# Lan.net
KiCad netlist of a schematic drawn in Altium Designer
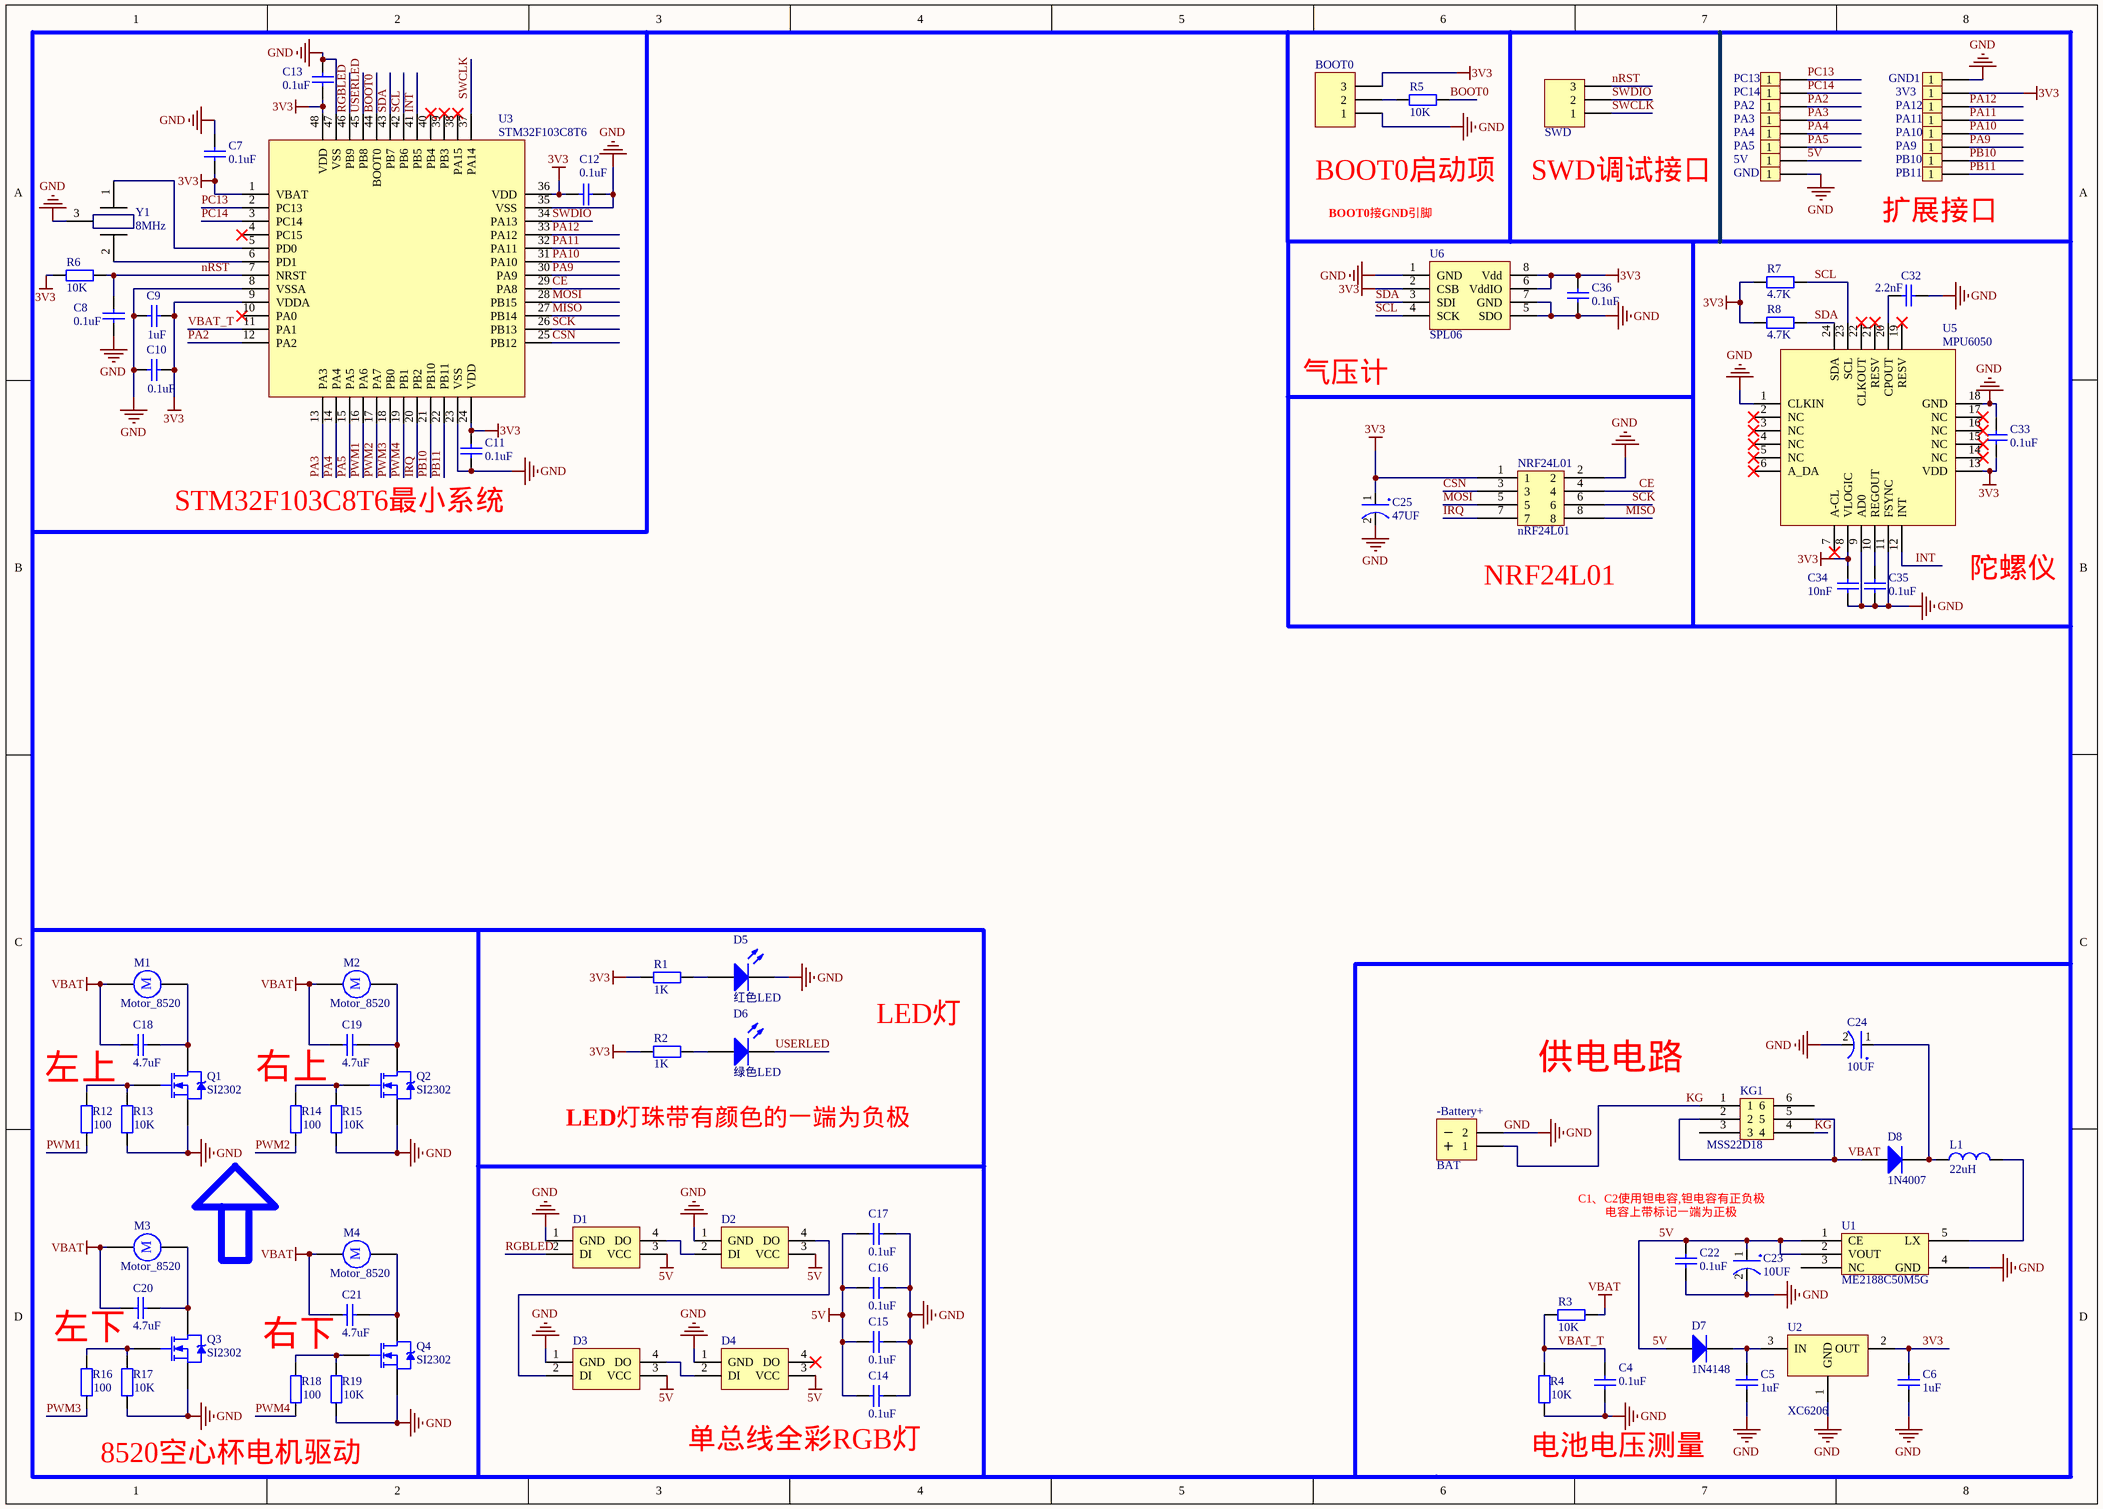
[diagram p0: Lan.SchDoc]

(export (version "E")
  (design (tool "Eeschema 10.0.6"))
  (components
    (comp (ref "-Battery+")
      (value "BAT")
      (footprint "BAT")
      (description "两脚排针")
      (fields (field (name "PUBLISHER") "mazhongwei"))
      (libsource (lib "RoboFly") (part "BAT"))
    )
    (comp (ref "3V3")
      (value "Header 1")
      (footprint "HEADER1")
      (description "单排针")
      (fields (field (name "PUBLISHER") "Altium Limited"))
      (libsource (lib "RoboFly") (part "Header 1"))
    )
    (comp (ref "5V")
      (value "Header 1")
      (footprint "HEADER1")
      (description "单排针")
      (fields (field (name "PUBLISHER") "Altium Limited"))
      (libsource (lib "RoboFly") (part "Header 1"))
    )
    (comp (ref "BOOT0")
      (value "BOOT")
      (footprint "HEADER1X3")
      (description "三脚排针")
      (fields (field (name "PUBLISHER") "Altium Limited"))
      (libsource (lib "RoboFly") (part "Header 3"))
    )
    (comp (ref "C4")
      (value "0.1uF")
      (footprint "C_0603")
      (description "0603贴片电容")
      (fields (field (name "PUBLISHER") "Altium Limited"))
      (libsource (lib "RoboFly") (part "C_0603"))
    )
    (comp (ref "C5")
      (value "1uF")
      (footprint "C_0603")
      (description "0603贴片电容")
      (fields (field (name "PUBLISHER") "Altium Limited"))
      (libsource (lib "RoboFly") (part "C_0603"))
    )
    (comp (ref "C6")
      (value "1uF")
      (footprint "C_0603")
      (description "0603贴片电容")
      (fields (field (name "PUBLISHER") "Altium Limited"))
      (libsource (lib "RoboFly") (part "C_0603"))
    )
    (comp (ref "C7")
      (value "0.1uF")
      (footprint "C_0603")
      (description "0603贴片电容")
      (fields (field (name "PUBLISHER") "Altium Limited"))
      (libsource (lib "RoboFly") (part "C_0603"))
    )
    (comp (ref "C8")
      (value "0.1uF")
      (footprint "C_0603")
      (description "0603贴片电容")
      (fields (field (name "PUBLISHER") "Altium Limited"))
      (libsource (lib "RoboFly") (part "C_0603"))
    )
    (comp (ref "C9")
      (value "1uF")
      (footprint "C_0603")
      (description "0603贴片电容")
      (fields (field (name "PUBLISHER") "Altium Limited"))
      (libsource (lib "RoboFly") (part "C_0603"))
    )
    (comp (ref "C10")
      (value "0.1uF")
      (footprint "C_0603")
      (description "0603贴片电容")
      (fields (field (name "PUBLISHER") "Altium Limited"))
      (libsource (lib "RoboFly") (part "C_0603"))
    )
    (comp (ref "C11")
      (value "0.1uF")
      (footprint "C_0603")
      (description "0603贴片电容")
      (fields (field (name "PUBLISHER") "Altium Limited"))
      (libsource (lib "RoboFly") (part "C_0603"))
    )
    (comp (ref "C12")
      (value "0.1uF")
      (footprint "C_0603")
      (description "0603贴片电容")
      (fields (field (name "PUBLISHER") "Altium Limited"))
      (libsource (lib "RoboFly") (part "C_0603"))
    )
    (comp (ref "C13")
      (value "0.1uF")
      (footprint "C_0603")
      (description "0603贴片电容")
      (fields (field (name "PUBLISHER") "Altium Limited"))
      (libsource (lib "RoboFly") (part "C_0603"))
    )
    (comp (ref "C14")
      (value "0.1uF")
      (footprint "C_0603")
      (description "0603贴片电容")
      (fields (field (name "PUBLISHER") "Altium Limited"))
      (libsource (lib "RoboFly") (part "C_0603"))
    )
    (comp (ref "C15")
      (value "0.1uF")
      (footprint "C_0603")
      (description "0603贴片电容")
      (fields (field (name "PUBLISHER") "Altium Limited"))
      (libsource (lib "RoboFly") (part "C_0603"))
    )
    (comp (ref "C16")
      (value "0.1uF")
      (footprint "C_0603")
      (description "0603贴片电容")
      (fields (field (name "PUBLISHER") "Altium Limited"))
      (libsource (lib "RoboFly") (part "C_0603"))
    )
    (comp (ref "C17")
      (value "0.1uF")
      (footprint "C_0603")
      (description "0603贴片电容")
      (fields (field (name "PUBLISHER") "Altium Limited"))
      (libsource (lib "RoboFly") (part "C_0603"))
    )
    (comp (ref "C18")
      (value "4.7uF")
      (footprint "C_0603")
      (description "0603贴片电容")
      (fields (field (name "PUBLISHER") "Altium Limited"))
      (libsource (lib "RoboFly") (part "C_0603"))
    )
    (comp (ref "C19")
      (value "4.7uF")
      (footprint "C_0603")
      (description "0603贴片电容")
      (fields (field (name "PUBLISHER") "Altium Limited"))
      (libsource (lib "RoboFly") (part "C_0603"))
    )
    (comp (ref "C20")
      (value "4.7uF")
      (footprint "C_0603")
      (description "0603贴片电容")
      (fields (field (name "PUBLISHER") "Altium Limited"))
      (libsource (lib "RoboFly") (part "C_0603"))
    )
    (comp (ref "C21")
      (value "4.7uF")
      (footprint "C_0603")
      (description "0603贴片电容")
      (fields (field (name "PUBLISHER") "Altium Limited"))
      (libsource (lib "RoboFly") (part "C_0603"))
    )
    (comp (ref "C22")
      (value "0.1uF")
      (footprint "C_0603")
      (description "0603贴片电容")
      (fields (field (name "PUBLISHER") "Altium Limited"))
      (libsource (lib "RoboFly") (part "C_0603"))
    )
    (comp (ref "C23")
      (value "10UF")
      (footprint "capacity")
      (description "3216钽电容")
      (libsource (lib "RoboFly") (part "capacity"))
    )
    (comp (ref "C24")
      (value "10UF")
      (footprint "capacity")
      (description "3216钽电容")
      (libsource (lib "RoboFly") (part "capacity"))
    )
    (comp (ref "C25")
      (value "47UF")
      (footprint "capacity")
      (description "3216钽电容")
      (libsource (lib "RoboFly") (part "capacity"))
    )
    (comp (ref "C32")
      (value "2.2nF")
      (footprint "C_0603")
      (description "0603贴片电容")
      (fields (field (name "PUBLISHER") "Altium Limited"))
      (libsource (lib "RoboFly") (part "C_0603"))
    )
    (comp (ref "C33")
      (value "0.1uF")
      (footprint "C_0603")
      (description "0603贴片电容")
      (fields (field (name "PUBLISHER") "Altium Limited"))
      (libsource (lib "RoboFly") (part "C_0603"))
    )
    (comp (ref "C34")
      (value "10nF")
      (footprint "C_0603")
      (description "0603贴片电容")
      (fields (field (name "PUBLISHER") "Altium Limited"))
      (libsource (lib "RoboFly") (part "C_0603"))
    )
    (comp (ref "C35")
      (value "0.1uF")
      (footprint "C_0603")
      (description "0603贴片电容")
      (fields (field (name "PUBLISHER") "Altium Limited"))
      (libsource (lib "RoboFly") (part "C_0603"))
    )
    (comp (ref "C36")
      (value "0.1uF")
      (footprint "C_0603")
      (description "0603贴片电容")
      (fields (field (name "PUBLISHER") "Altium Limited"))
      (libsource (lib "RoboFly") (part "C_0603"))
    )
    (comp (ref "D1")
      (value "WS2812B")
      (footprint "RGB_LED_5050")
      (description "单总线全彩RGB灯")
      (fields (field (name "PUBLISHER") "mazhongwei"))
      (libsource (lib "RoboFly") (part "P923D"))
    )
    (comp (ref "D2")
      (value "WS2812B")
      (footprint "RGB_LED_5050")
      (description "单总线全彩RGB灯")
      (fields (field (name "PUBLISHER") "mazhongwei"))
      (libsource (lib "RoboFly") (part "P923D"))
    )
    (comp (ref "D3")
      (value "WS2812B")
      (footprint "RGB_LED_5050")
      (description "单总线全彩RGB灯")
      (fields (field (name "PUBLISHER") "mazhongwei"))
      (libsource (lib "RoboFly") (part "P923D"))
    )
    (comp (ref "D4")
      (value "WS2812B")
      (footprint "RGB_LED_5050")
      (description "单总线全彩RGB灯")
      (fields (field (name "PUBLISHER") "mazhongwei"))
      (libsource (lib "RoboFly") (part "P923D"))
    )
    (comp (ref "D5")
      (value "红色LED")
      (footprint "LED-0603")
      (description "发光二极管")
      (fields (field (name "PUBLISHER") "Altium Limited"))
      (libsource (lib "RoboFly") (part "LED 0603"))
    )
    (comp (ref "D6")
      (value "绿色LED")
      (footprint "LED-0603")
      (description "发光二极管")
      (fields (field (name "PUBLISHER") "Altium Limited"))
      (libsource (lib "RoboFly") (part "LED 0603"))
    )
    (comp (ref "D7")
      (value "1N4148")
      (footprint "SOD-123")
      (description "Default Diode")
      (fields (field (name "PUBLISHER") "mazhongwei"))
      (libsource (lib "RoboFly") (part "Diode"))
    )
    (comp (ref "D8")
      (value "1N4007")
      (footprint "SMA")
      (description "Default Diode")
      (fields (field (name "PUBLISHER") "mazhongwei"))
      (libsource (lib "RoboFly") (part "Diode"))
    )
    (comp (ref "GND")
      (value "Header 1")
      (footprint "HEADER1")
      (description "单排针")
      (fields (field (name "PUBLISHER") "Altium Limited"))
      (libsource (lib "RoboFly") (part "Header 1"))
    )
    (comp (ref "GND1")
      (value "Header 1")
      (footprint "HEADER1")
      (description "单排针")
      (fields (field (name "PUBLISHER") "Altium Limited"))
      (libsource (lib "RoboFly") (part "Header 1"))
    )
    (comp (ref "KG1")
      (value "MSS22D18")
      (footprint "MSS22D18")
      (description "拨动开关")
      (libsource (lib "RoboFly") (part "MSS22D18"))
    )
    (comp (ref "L1")
      (value "22uH")
      (footprint "22uH")
      (description "电感")
      (fields (field (name "PUBLISHER") "Altium Limited"))
      (libsource (lib "RoboFly") (part "Inductor"))
    )
    (comp (ref "M1")
      (value "Motor_8520")
      (footprint "MOTOR")
      (description "Motor, General Kind")
      (fields (field (name "PUBLISHER") "mazhongwei"))
      (libsource (lib "RoboFly") (part "Motor_720"))
    )
    (comp (ref "M2")
      (value "Motor_8520")
      (footprint "MOTOR")
      (description "Motor, General Kind")
      (fields (field (name "PUBLISHER") "mazhongwei"))
      (libsource (lib "RoboFly") (part "Motor_720"))
    )
    (comp (ref "M3")
      (value "Motor_8520")
      (footprint "MOTOR")
      (description "Motor, General Kind")
      (fields (field (name "PUBLISHER") "mazhongwei"))
      (libsource (lib "RoboFly") (part "Motor_720"))
    )
    (comp (ref "M4")
      (value "Motor_8520")
      (footprint "MOTOR")
      (description "Motor, General Kind")
      (fields (field (name "PUBLISHER") "mazhongwei"))
      (libsource (lib "RoboFly") (part "Motor_720"))
    )
    (comp (ref "NRF24L01")
      (value "nRF24L01")
      (footprint "NRF24L01")
      (description "2.4G模块")
      (libsource (lib "RoboFly") (part "nRF24L01"))
    )
    (comp (ref "PA2")
      (value "Header 1")
      (footprint "HEADER1")
      (description "单排针")
      (fields (field (name "PUBLISHER") "Altium Limited"))
      (libsource (lib "RoboFly") (part "Header 1"))
    )
    (comp (ref "PA3")
      (value "Header 1")
      (footprint "HEADER1")
      (description "单排针")
      (fields (field (name "PUBLISHER") "Altium Limited"))
      (libsource (lib "RoboFly") (part "Header 1"))
    )
    (comp (ref "PA4")
      (value "Header 1")
      (footprint "HEADER1")
      (description "单排针")
      (fields (field (name "PUBLISHER") "Altium Limited"))
      (libsource (lib "RoboFly") (part "Header 1"))
    )
    (comp (ref "PA5")
      (value "Header 1")
      (footprint "HEADER1")
      (description "单排针")
      (fields (field (name "PUBLISHER") "Altium Limited"))
      (libsource (lib "RoboFly") (part "Header 1"))
    )
    (comp (ref "PA9")
      (value "Header 1")
      (footprint "HEADER1")
      (description "单排针")
      (fields (field (name "PUBLISHER") "Altium Limited"))
      (libsource (lib "RoboFly") (part "Header 1"))
    )
    (comp (ref "PA10")
      (value "Header 1")
      (footprint "HEADER1")
      (description "单排针")
      (fields (field (name "PUBLISHER") "Altium Limited"))
      (libsource (lib "RoboFly") (part "Header 1"))
    )
    (comp (ref "PA11")
      (value "Header 1")
      (footprint "HEADER1")
      (description "单排针")
      (fields (field (name "PUBLISHER") "Altium Limited"))
      (libsource (lib "RoboFly") (part "Header 1"))
    )
    (comp (ref "PA12")
      (value "Header 1")
      (footprint "HEADER1")
      (description "单排针")
      (fields (field (name "PUBLISHER") "Altium Limited"))
      (libsource (lib "RoboFly") (part "Header 1"))
    )
    (comp (ref "PB10")
      (value "Header 1")
      (footprint "HEADER1")
      (description "单排针")
      (fields (field (name "PUBLISHER") "Altium Limited"))
      (libsource (lib "RoboFly") (part "Header 1"))
    )
    (comp (ref "PB11")
      (value "Header 1")
      (footprint "HEADER1")
      (description "单排针")
      (fields (field (name "PUBLISHER") "Altium Limited"))
      (libsource (lib "RoboFly") (part "Header 1"))
    )
    (comp (ref "PC13")
      (value "Header 1")
      (footprint "HEADER1")
      (description "单排针")
      (fields (field (name "PUBLISHER") "Altium Limited"))
      (libsource (lib "RoboFly") (part "Header 1"))
    )
    (comp (ref "PC14")
      (value "Header 1")
      (footprint "HEADER1")
      (description "单排针")
      (fields (field (name "PUBLISHER") "Altium Limited"))
      (libsource (lib "RoboFly") (part "Header 1"))
    )
    (comp (ref "Q1")
      (value "SI2302")
      (footprint "SOT-23(SOT-23-3)")
      (description "N-Channel Power MOSFET")
      (fields (field (name "PUBLISHER") "mazhongwei"))
      (libsource (lib "RoboFly") (part "SI2302"))
    )
    (comp (ref "Q2")
      (value "SI2302")
      (footprint "SOT-23(SOT-23-3)")
      (description "N-Channel Power MOSFET")
      (fields (field (name "PUBLISHER") "mazhongwei"))
      (libsource (lib "RoboFly") (part "SI2302"))
    )
    (comp (ref "Q3")
      (value "SI2302")
      (footprint "SOT-23(SOT-23-3)")
      (description "N-Channel Power MOSFET")
      (fields (field (name "PUBLISHER") "mazhongwei"))
      (libsource (lib "RoboFly") (part "SI2302"))
    )
    (comp (ref "Q4")
      (value "SI2302")
      (footprint "SOT-23(SOT-23-3)")
      (description "N-Channel Power MOSFET")
      (fields (field (name "PUBLISHER") "mazhongwei"))
      (libsource (lib "RoboFly") (part "SI2302"))
    )
    (comp (ref "R1")
      (value "1K")
      (footprint "R_0603")
      (description "0603贴片电阻")
      (fields (field (name "PUBLISHER") "Altium Limited"))
      (libsource (lib "Lan") (part "R_0603"))
    )
    (comp (ref "R2")
      (value "1K")
      (footprint "R_0603")
      (description "0603贴片电阻")
      (fields (field (name "PUBLISHER") "Altium Limited"))
      (libsource (lib "Lan") (part "R_0603"))
    )
    (comp (ref "R3")
      (value "10K")
      (footprint "R_0603")
      (description "0603贴片电阻")
      (fields (field (name "PUBLISHER") "Altium Limited"))
      (libsource (lib "Lan") (part "R_0603"))
    )
    (comp (ref "R4")
      (value "10K")
      (footprint "R_0603")
      (description "0603贴片电阻")
      (fields (field (name "PUBLISHER") "Altium Limited"))
      (libsource (lib "") (part "R_0603_1"))
    )
    (comp (ref "R5")
      (value "10K")
      (footprint "R_0603")
      (description "0603贴片电阻")
      (fields (field (name "PUBLISHER") "Altium Limited"))
      (libsource (lib "Lan") (part "R_0603"))
    )
    (comp (ref "R6")
      (value "10K")
      (footprint "R_0603")
      (description "0603贴片电阻")
      (fields (field (name "PUBLISHER") "Altium Limited"))
      (libsource (lib "") (part "R_0603_2"))
    )
    (comp (ref "R7")
      (value "4.7K")
      (footprint "R_0603")
      (description "0603贴片电阻")
      (fields (field (name "PUBLISHER") "Altium Limited"))
      (libsource (lib "Lan") (part "R_0603"))
    )
    (comp (ref "R8")
      (value "4.7K")
      (footprint "R_0603")
      (description "0603贴片电阻")
      (fields (field (name "PUBLISHER") "Altium Limited"))
      (libsource (lib "Lan") (part "R_0603"))
    )
    (comp (ref "R12")
      (value "100")
      (footprint "R_0603")
      (description "0603贴片电阻")
      (fields (field (name "PUBLISHER") "Altium Limited"))
      (libsource (lib "") (part "R_0603_1"))
    )
    (comp (ref "R13")
      (value "10K")
      (footprint "R_0603")
      (description "0603贴片电阻")
      (fields (field (name "PUBLISHER") "Altium Limited"))
      (libsource (lib "") (part "R_0603_1"))
    )
    (comp (ref "R14")
      (value "100")
      (footprint "R_0603")
      (description "0603贴片电阻")
      (fields (field (name "PUBLISHER") "Altium Limited"))
      (libsource (lib "") (part "R_0603_1"))
    )
    (comp (ref "R15")
      (value "10K")
      (footprint "R_0603")
      (description "0603贴片电阻")
      (fields (field (name "PUBLISHER") "Altium Limited"))
      (libsource (lib "") (part "R_0603_1"))
    )
    (comp (ref "R16")
      (value "100")
      (footprint "R_0603")
      (description "0603贴片电阻")
      (fields (field (name "PUBLISHER") "Altium Limited"))
      (libsource (lib "") (part "R_0603_1"))
    )
    (comp (ref "R17")
      (value "10K")
      (footprint "R_0603")
      (description "0603贴片电阻")
      (fields (field (name "PUBLISHER") "Altium Limited"))
      (libsource (lib "") (part "R_0603_1"))
    )
    (comp (ref "R18")
      (value "100")
      (footprint "R_0603")
      (description "0603贴片电阻")
      (fields (field (name "PUBLISHER") "Altium Limited"))
      (libsource (lib "") (part "R_0603_1"))
    )
    (comp (ref "R19")
      (value "10K")
      (footprint "R_0603")
      (description "0603贴片电阻")
      (fields (field (name "PUBLISHER") "Altium Limited"))
      (libsource (lib "") (part "R_0603_1"))
    )
    (comp (ref "SWD")
      (value "SWD")
      (footprint "SH1_0X5P_WT")
      (description "三脚排针")
      (fields (field (name "PUBLISHER") "Altium Limited"))
      (libsource (lib "RoboFly") (part "SWD"))
    )
    (comp (ref "U1")
      (value "ME2188C50M5G")
      (footprint "ME2188C50M5G")
      (description "升压IC")
      (libsource (lib "RoboFly") (part "ME2188C50M5G"))
    )
    (comp (ref "U2")
      (value "XC6206")
      (footprint "SOT-23(SOT-23-3)")
      (description "稳压LDO")
      (fields (field (name "PUBLISHER") "mazhongwei"))
      (libsource (lib "Lan") (part "XC6206"))
    )
    (comp (ref "U3")
      (value "STM32F103C8T6")
      (footprint "LQFP-48_7x7x05P")
      (libsource (lib "RoboFly") (part "STM32F103C8T6"))
    )
    (comp (ref "U5")
      (value "MPU6050")
      (footprint "QFN-24_4x4x05P")
      (description "陀螺仪")
      (libsource (lib "RoboFly") (part "MPU6050"))
    )
    (comp (ref "U6")
      (value "SPL06")
      (footprint "LGA-2_5X2MM")
      (description "气压计")
      (fields (field (name "PUBLISHER") "mazhongwei"))
      (libsource (lib "RoboFly") (part "FBM320"))
    )
    (comp (ref "Y1")
      (value "8MHz")
      (footprint "SMD-CSTSE800G52-R0")
      (description "贴片8MHZ晶振")
      (fields (field (name "Comment") "XTAL") (field (name "PUBLISHER") "mazhongwei"))
      (libsource (lib "RoboFly") (part "XTAL_2"))
    )
  )
  (nets
    (net (code "1") (name "/BOOT0") (class "Default")
      (node (ref "R5") (pin "2") (pinfunction "2_2") (pintype "passive"))
      (node (ref "U3") (pin "44") (pinfunction "BOOT0_44") (pintype "passive"))
    )
    (net (code "2") (name "/CE") (class "Default")
      (node (ref "NRF24L01") (pin "4") (pinfunction "4_4") (pintype "passive"))
      (node (ref "U3") (pin "29") (pinfunction "PA8_29") (pintype "passive"))
    )
    (net (code "3") (name "/CSN") (class "Default")
      (node (ref "NRF24L01") (pin "3") (pinfunction "3_3") (pintype "passive"))
      (node (ref "U3") (pin "25") (pinfunction "PB12_25") (pintype "passive"))
    )
    (net (code "4") (name "/INT") (class "Default")
      (node (ref "U3") (pin "41") (pinfunction "PB5_41") (pintype "passive"))
      (node (ref "U5") (pin "12") (pinfunction "INT_12") (pintype "passive"))
    )
    (net (code "5") (name "/IRQ") (class "Default")
      (node (ref "NRF24L01") (pin "7") (pinfunction "7_7") (pintype "passive"))
      (node (ref "U3") (pin "20") (pinfunction "PB2_20") (pintype "passive"))
    )
    (net (code "6") (name "/KG") (class "Default")
      (node (ref "-Battery+") (pin "1") (pinfunction "1_1") (pintype "passive"))
      (node (ref "KG1") (pin "1") (pinfunction "1_1") (pintype "passive"))
      (node (ref "KG1") (pin "4") (pinfunction "4_4") (pintype "passive"))
    )
    (net (code "7") (name "/MISO") (class "Default")
      (node (ref "NRF24L01") (pin "8") (pinfunction "8_8") (pintype "passive"))
      (node (ref "U3") (pin "27") (pinfunction "PB14_27") (pintype "passive"))
    )
    (net (code "8") (name "/MOSI") (class "Default")
      (node (ref "NRF24L01") (pin "5") (pinfunction "5_5") (pintype "passive"))
      (node (ref "U3") (pin "28") (pinfunction "PB15_28") (pintype "passive"))
    )
    (net (code "9") (name "/PA2") (class "Default")
      (node (ref "PA2") (pin "1") (pinfunction "1_1") (pintype "passive"))
      (node (ref "U3") (pin "12") (pinfunction "PA2_12") (pintype "passive"))
    )
    (net (code "10") (name "/PA3") (class "Default")
      (node (ref "PA3") (pin "1") (pinfunction "1_1") (pintype "passive"))
      (node (ref "U3") (pin "13") (pinfunction "PA3_13") (pintype "passive"))
    )
    (net (code "11") (name "/PA4") (class "Default")
      (node (ref "PA4") (pin "1") (pinfunction "1_1") (pintype "passive"))
      (node (ref "U3") (pin "14") (pinfunction "PA4_14") (pintype "passive"))
    )
    (net (code "12") (name "/PA5") (class "Default")
      (node (ref "PA5") (pin "1") (pinfunction "1_1") (pintype "passive"))
      (node (ref "U3") (pin "15") (pinfunction "PA5_15") (pintype "passive"))
    )
    (net (code "13") (name "/PA9") (class "Default")
      (node (ref "PA9") (pin "1") (pinfunction "1_1") (pintype "passive"))
      (node (ref "U3") (pin "30") (pinfunction "PA9_30") (pintype "passive"))
    )
    (net (code "14") (name "/PA10") (class "Default")
      (node (ref "PA10") (pin "1") (pinfunction "1_1") (pintype "passive"))
      (node (ref "U3") (pin "31") (pinfunction "PA10_31") (pintype "passive"))
    )
    (net (code "15") (name "/PA11") (class "Default")
      (node (ref "PA11") (pin "1") (pinfunction "1_1") (pintype "passive"))
      (node (ref "U3") (pin "32") (pinfunction "PA11_32") (pintype "passive"))
    )
    (net (code "16") (name "/PA12") (class "Default")
      (node (ref "PA12") (pin "1") (pinfunction "1_1") (pintype "passive"))
      (node (ref "U3") (pin "33") (pinfunction "PA12_33") (pintype "passive"))
    )
    (net (code "17") (name "/PB10") (class "Default")
      (node (ref "PB10") (pin "1") (pinfunction "1_1") (pintype "passive"))
      (node (ref "U3") (pin "21") (pinfunction "PB10_21") (pintype "passive"))
    )
    (net (code "18") (name "/PB11") (class "Default")
      (node (ref "PB11") (pin "1") (pinfunction "1_1") (pintype "passive"))
      (node (ref "U3") (pin "22") (pinfunction "PB11_22") (pintype "passive"))
    )
    (net (code "19") (name "/PC13") (class "Default")
      (node (ref "PC13") (pin "1") (pinfunction "1_1") (pintype "passive"))
      (node (ref "U3") (pin "2") (pinfunction "PC13_2") (pintype "passive"))
    )
    (net (code "20") (name "/PC14") (class "Default")
      (node (ref "PC14") (pin "1") (pinfunction "1_1") (pintype "passive"))
      (node (ref "U3") (pin "3") (pinfunction "PC14_3") (pintype "passive"))
    )
    (net (code "21") (name "/PWM1") (class "Default")
      (node (ref "R12") (pin "1") (pinfunction "1_1") (pintype "passive"))
      (node (ref "U3") (pin "16") (pinfunction "PA6_16") (pintype "passive"))
    )
    (net (code "22") (name "/PWM2") (class "Default")
      (node (ref "R14") (pin "1") (pinfunction "1_1") (pintype "passive"))
      (node (ref "U3") (pin "17") (pinfunction "PA7_17") (pintype "passive"))
    )
    (net (code "23") (name "/PWM3") (class "Default")
      (node (ref "R16") (pin "1") (pinfunction "1_1") (pintype "passive"))
      (node (ref "U3") (pin "18") (pinfunction "PB0_18") (pintype "passive"))
    )
    (net (code "24") (name "/PWM4") (class "Default")
      (node (ref "R18") (pin "1") (pinfunction "1_1") (pintype "passive"))
      (node (ref "U3") (pin "19") (pinfunction "PB1_19") (pintype "passive"))
    )
    (net (code "25") (name "/RGBLED") (class "Default")
      (node (ref "D1") (pin "2") (pinfunction "DI_2") (pintype "passive"))
      (node (ref "U3") (pin "46") (pinfunction "PB9_46") (pintype "passive"))
    )
    (net (code "26") (name "/SCK") (class "Default")
      (node (ref "NRF24L01") (pin "6") (pinfunction "6_6") (pintype "passive"))
      (node (ref "U3") (pin "26") (pinfunction "PB13_26") (pintype "passive"))
    )
    (net (code "27") (name "/SCL") (class "Default")
      (node (ref "R7") (pin "2") (pinfunction "2_2") (pintype "passive"))
      (node (ref "U3") (pin "42") (pinfunction "PB6_42") (pintype "passive"))
      (node (ref "U5") (pin "23") (pinfunction "SCL_23") (pintype "passive"))
      (node (ref "U6") (pin "4") (pinfunction "SCK_4") (pintype "passive"))
    )
    (net (code "28") (name "/SDA") (class "Default")
      (node (ref "R8") (pin "2") (pinfunction "2_2") (pintype "passive"))
      (node (ref "U3") (pin "43") (pinfunction "PB7_43") (pintype "passive"))
      (node (ref "U5") (pin "24") (pinfunction "SDA_24") (pintype "passive"))
      (node (ref "U6") (pin "3") (pinfunction "SDI_3") (pintype "passive"))
    )
    (net (code "29") (name "/SWCLK") (class "Default")
      (node (ref "SWD") (pin "1") (pinfunction "1_1") (pintype "passive"))
      (node (ref "U3") (pin "37") (pinfunction "PA14_37") (pintype "passive"))
    )
    (net (code "30") (name "/SWDIO") (class "Default")
      (node (ref "SWD") (pin "2") (pinfunction "2_2") (pintype "passive"))
      (node (ref "U3") (pin "34") (pinfunction "PA13_34") (pintype "passive"))
    )
    (net (code "31") (name "/USERLED") (class "Default")
      (node (ref "D6") (pin "2") (pinfunction "2_2") (pintype "passive"))
      (node (ref "U3") (pin "45") (pinfunction "PB8_45") (pintype "passive"))
    )
    (net (code "32") (name "/VBAT_T") (class "Default")
      (node (ref "C4") (pin "2") (pinfunction "2_2") (pintype "passive"))
      (node (ref "R3") (pin "1") (pinfunction "1_1") (pintype "passive"))
      (node (ref "R4") (pin "2") (pinfunction "2_2") (pintype "passive"))
      (node (ref "U3") (pin "11") (pinfunction "PA1_11") (pintype "passive"))
    )
    (net (code "33") (name "/nRST") (class "Default")
      (node (ref "C8") (pin "2") (pinfunction "2_2") (pintype "passive"))
      (node (ref "R6") (pin "1") (pinfunction "1_1") (pintype "passive"))
      (node (ref "SWD") (pin "3") (pinfunction "3_3") (pintype "passive"))
      (node (ref "U3") (pin "7") (pinfunction "NRST_7") (pintype "passive"))
    )
    (net (code "34") (name "3V3") (class "Default")
      (node (ref "3V3") (pin "1") (pinfunction "1_1") (pintype "passive"))
      (node (ref "BOOT0") (pin "3") (pinfunction "3_3") (pintype "passive"))
      (node (ref "C10") (pin "2") (pinfunction "2_2") (pintype "passive"))
      (node (ref "C11") (pin "1") (pinfunction "1_1") (pintype "passive"))
      (node (ref "C12") (pin "2") (pinfunction "2_2") (pintype "passive"))
      (node (ref "C13") (pin "1") (pinfunction "1_1") (pintype "passive"))
      (node (ref "C25") (pin "1") (pinfunction "1_1") (pintype "passive"))
      (node (ref "C33") (pin "2") (pinfunction "2_2") (pintype "passive"))
      (node (ref "C34") (pin "2") (pinfunction "2_2") (pintype "passive"))
      (node (ref "C36") (pin "1") (pinfunction "1_1") (pintype "passive"))
      (node (ref "C6") (pin "1") (pinfunction "1_1") (pintype "passive"))
      (node (ref "C7") (pin "2") (pinfunction "2_2") (pintype "passive"))
      (node (ref "C9") (pin "2") (pinfunction "2_2") (pintype "passive"))
      (node (ref "NRF24L01") (pin "1") (pinfunction "1_1") (pintype "passive"))
      (node (ref "R1") (pin "1") (pinfunction "1_1") (pintype "passive"))
      (node (ref "R2") (pin "1") (pinfunction "1_1") (pintype "passive"))
      (node (ref "R6") (pin "2") (pinfunction "2_2") (pintype "passive"))
      (node (ref "R7") (pin "1") (pinfunction "1_1") (pintype "passive"))
      (node (ref "R8") (pin "1") (pinfunction "1_1") (pintype "passive"))
      (node (ref "U2") (pin "2") (pinfunction "OUT_2") (pintype "passive"))
      (node (ref "U3") (pin "1") (pinfunction "VBAT_1") (pintype "passive"))
      (node (ref "U3") (pin "24") (pinfunction "VDD_24") (pintype "passive"))
      (node (ref "U3") (pin "36") (pinfunction "VDD_36") (pintype "passive"))
      (node (ref "U3") (pin "48") (pinfunction "VDD_48") (pintype "passive"))
      (node (ref "U3") (pin "9") (pinfunction "VDDA_9") (pintype "passive"))
      (node (ref "U5") (pin "13") (pinfunction "VDD_13") (pintype "passive"))
      (node (ref "U5") (pin "8") (pinfunction "VLOGIC_8") (pintype "passive"))
      (node (ref "U6") (pin "2") (pinfunction "CSB_2") (pintype "passive"))
      (node (ref "U6") (pin "6") (pinfunction "VddIO_6") (pintype "passive"))
      (node (ref "U6") (pin "8") (pinfunction "Vdd_8") (pintype "passive"))
    )
    (net (code "35") (name "5V") (class "Default")
      (node (ref "5V") (pin "1") (pinfunction "1_1") (pintype "passive"))
      (node (ref "C14") (pin "2") (pinfunction "2_2") (pintype "passive"))
      (node (ref "C15") (pin "2") (pinfunction "2_2") (pintype "passive"))
      (node (ref "C16") (pin "2") (pinfunction "2_2") (pintype "passive"))
      (node (ref "C17") (pin "2") (pinfunction "2_2") (pintype "passive"))
      (node (ref "C22") (pin "1") (pinfunction "1_1") (pintype "passive"))
      (node (ref "C23") (pin "1") (pinfunction "1_1") (pintype "passive"))
      (node (ref "D1") (pin "3") (pinfunction "VCC_3") (pintype "passive"))
      (node (ref "D2") (pin "3") (pinfunction "VCC_3") (pintype "passive"))
      (node (ref "D3") (pin "3") (pinfunction "VCC_3") (pintype "passive"))
      (node (ref "D4") (pin "3") (pinfunction "VCC_3") (pintype "passive"))
      (node (ref "D7") (pin "1") (pinfunction "A_1") (pintype "passive"))
      (node (ref "U1") (pin "1") (pinfunction "CE_1") (pintype "passive"))
      (node (ref "U1") (pin "2") (pinfunction "VOUT_2") (pintype "passive"))
    )
    (net (code "36") (name "GND") (class "Default")
      (node (ref "-Battery+") (pin "2") (pinfunction "2_2") (pintype "passive"))
      (node (ref "BOOT0") (pin "1") (pinfunction "1_1") (pintype "passive"))
      (node (ref "C10") (pin "1") (pinfunction "1_1") (pintype "passive"))
      (node (ref "C11") (pin "2") (pinfunction "2_2") (pintype "passive"))
      (node (ref "C12") (pin "1") (pinfunction "1_1") (pintype "passive"))
      (node (ref "C13") (pin "2") (pinfunction "2_2") (pintype "passive"))
      (node (ref "C14") (pin "1") (pinfunction "1_1") (pintype "passive"))
      (node (ref "C15") (pin "1") (pinfunction "1_1") (pintype "passive"))
      (node (ref "C16") (pin "1") (pinfunction "1_1") (pintype "passive"))
      (node (ref "C17") (pin "1") (pinfunction "1_1") (pintype "passive"))
      (node (ref "C22") (pin "2") (pinfunction "2_2") (pintype "passive"))
      (node (ref "C23") (pin "2") (pinfunction "2_2") (pintype "passive"))
      (node (ref "C24") (pin "2") (pinfunction "2_2") (pintype "passive"))
      (node (ref "C25") (pin "2") (pinfunction "2_2") (pintype "passive"))
      (node (ref "C32") (pin "1") (pinfunction "1_1") (pintype "passive"))
      (node (ref "C33") (pin "1") (pinfunction "1_1") (pintype "passive"))
      (node (ref "C34") (pin "1") (pinfunction "1_1") (pintype "passive"))
      (node (ref "C35") (pin "2") (pinfunction "2_2") (pintype "passive"))
      (node (ref "C36") (pin "2") (pinfunction "2_2") (pintype "passive"))
      (node (ref "C4") (pin "1") (pinfunction "1_1") (pintype "passive"))
      (node (ref "C5") (pin "2") (pinfunction "2_2") (pintype "passive"))
      (node (ref "C6") (pin "2") (pinfunction "2_2") (pintype "passive"))
      (node (ref "C7") (pin "1") (pinfunction "1_1") (pintype "passive"))
      (node (ref "C8") (pin "1") (pinfunction "1_1") (pintype "passive"))
      (node (ref "C9") (pin "1") (pinfunction "1_1") (pintype "passive"))
      (node (ref "D1") (pin "1") (pinfunction "GND_1") (pintype "passive"))
      (node (ref "D2") (pin "1") (pinfunction "GND_1") (pintype "passive"))
      (node (ref "D3") (pin "1") (pinfunction "GND_1") (pintype "passive"))
      (node (ref "D4") (pin "1") (pinfunction "GND_1") (pintype "passive"))
      (node (ref "D5") (pin "2") (pinfunction "2_2") (pintype "passive"))
      (node (ref "GND") (pin "1") (pinfunction "1_1") (pintype "passive"))
      (node (ref "GND1") (pin "1") (pinfunction "1_1") (pintype "passive"))
      (node (ref "NRF24L01") (pin "2") (pinfunction "2_2") (pintype "passive"))
      (node (ref "Q1") (pin "2") (pinfunction "S_2") (pintype "passive"))
      (node (ref "Q2") (pin "2") (pinfunction "S_2") (pintype "passive"))
      (node (ref "Q3") (pin "2") (pinfunction "S_2") (pintype "passive"))
      (node (ref "Q4") (pin "2") (pinfunction "S_2") (pintype "passive"))
      (node (ref "R13") (pin "1") (pinfunction "1_1") (pintype "passive"))
      (node (ref "R15") (pin "1") (pinfunction "1_1") (pintype "passive"))
      (node (ref "R17") (pin "1") (pinfunction "1_1") (pintype "passive"))
      (node (ref "R19") (pin "1") (pinfunction "1_1") (pintype "passive"))
      (node (ref "R4") (pin "1") (pinfunction "1_1") (pintype "passive"))
      (node (ref "U1") (pin "4") (pinfunction "GND_4") (pintype "passive"))
      (node (ref "U2") (pin "1") (pinfunction "GND_1") (pintype "passive"))
      (node (ref "U3") (pin "23") (pinfunction "VSS_23") (pintype "passive"))
      (node (ref "U3") (pin "35") (pinfunction "VSS_35") (pintype "passive"))
      (node (ref "U3") (pin "47") (pinfunction "VSS_47") (pintype "passive"))
      (node (ref "U3") (pin "8") (pinfunction "VSSA_8") (pintype "passive"))
      (node (ref "U5") (pin "1") (pinfunction "CLKIN_1") (pintype "passive"))
      (node (ref "U5") (pin "11") (pinfunction "FSYNC_11") (pintype "passive"))
      (node (ref "U5") (pin "18") (pinfunction "GND_18") (pintype "passive"))
      (node (ref "U5") (pin "9") (pinfunction "AD0_9") (pintype "passive"))
      (node (ref "U6") (pin "1") (pinfunction "GND_1") (pintype "passive"))
      (node (ref "U6") (pin "5") (pinfunction "SDO_5") (pintype "passive"))
      (node (ref "U6") (pin "7") (pinfunction "GND_7") (pintype "passive"))
      (node (ref "Y1") (pin "3") (pinfunction "3_3") (pintype "passive"))
    )
    (net (code "37") (name "Net-(BOOT0-Pad2)") (class "Default")
      (node (ref "BOOT0") (pin "2") (pinfunction "2_2") (pintype "passive"))
      (node (ref "R5") (pin "1") (pinfunction "1_1") (pintype "passive"))
    )
    (net (code "38") (name "Net-(D1-DO)") (class "Default")
      (node (ref "D1") (pin "4") (pinfunction "DO_4") (pintype "passive"))
      (node (ref "D2") (pin "2") (pinfunction "DI_2") (pintype "passive"))
    )
    (net (code "39") (name "Net-(D2-DO)") (class "Default")
      (node (ref "D2") (pin "4") (pinfunction "DO_4") (pintype "passive"))
      (node (ref "D3") (pin "2") (pinfunction "DI_2") (pintype "passive"))
    )
    (net (code "40") (name "Net-(D3-DO)") (class "Default")
      (node (ref "D3") (pin "4") (pinfunction "DO_4") (pintype "passive"))
      (node (ref "D4") (pin "2") (pinfunction "DI_2") (pintype "passive"))
    )
    (net (code "41") (name "Net-(D5-Pad1)") (class "Default")
      (node (ref "D5") (pin "1") (pinfunction "1_1") (pintype "passive"))
      (node (ref "R1") (pin "2") (pinfunction "2_2") (pintype "passive"))
    )
    (net (code "42") (name "Net-(D6-Pad1)") (class "Default")
      (node (ref "D6") (pin "1") (pinfunction "1_1") (pintype "passive"))
      (node (ref "R2") (pin "2") (pinfunction "2_2") (pintype "passive"))
    )
    (net (code "43") (name "Net-(D7-K)") (class "Default")
      (node (ref "C5") (pin "1") (pinfunction "1_1") (pintype "passive"))
      (node (ref "D7") (pin "2") (pinfunction "K_2") (pintype "passive"))
      (node (ref "U2") (pin "3") (pinfunction "IN_3") (pintype "passive"))
    )
    (net (code "44") (name "Net-(D8-K)") (class "Default")
      (node (ref "C24") (pin "1") (pinfunction "1_1") (pintype "passive"))
      (node (ref "D8") (pin "2") (pinfunction "K_2") (pintype "passive"))
      (node (ref "L1") (pin "1") (pinfunction "1_1") (pintype "passive"))
    )
    (net (code "45") (name "Net-(Q1-D)") (class "Default")
      (node (ref "C18") (pin "1") (pinfunction "1_1") (pintype "passive"))
      (node (ref "M1") (pin "2") (pinfunction "2_2") (pintype "passive"))
      (node (ref "Q1") (pin "3") (pinfunction "D_3") (pintype "passive"))
    )
    (net (code "46") (name "Net-(Q1-G)") (class "Default")
      (node (ref "Q1") (pin "1") (pinfunction "G_1") (pintype "passive"))
      (node (ref "R12") (pin "2") (pinfunction "2_2") (pintype "passive"))
      (node (ref "R13") (pin "2") (pinfunction "2_2") (pintype "passive"))
    )
    (net (code "47") (name "Net-(Q2-D)") (class "Default")
      (node (ref "C19") (pin "1") (pinfunction "1_1") (pintype "passive"))
      (node (ref "M2") (pin "2") (pinfunction "2_2") (pintype "passive"))
      (node (ref "Q2") (pin "3") (pinfunction "D_3") (pintype "passive"))
    )
    (net (code "48") (name "Net-(Q2-G)") (class "Default")
      (node (ref "Q2") (pin "1") (pinfunction "G_1") (pintype "passive"))
      (node (ref "R14") (pin "2") (pinfunction "2_2") (pintype "passive"))
      (node (ref "R15") (pin "2") (pinfunction "2_2") (pintype "passive"))
    )
    (net (code "49") (name "Net-(Q3-D)") (class "Default")
      (node (ref "C20") (pin "1") (pinfunction "1_1") (pintype "passive"))
      (node (ref "M3") (pin "2") (pinfunction "2_2") (pintype "passive"))
      (node (ref "Q3") (pin "3") (pinfunction "D_3") (pintype "passive"))
    )
    (net (code "50") (name "Net-(Q3-G)") (class "Default")
      (node (ref "Q3") (pin "1") (pinfunction "G_1") (pintype "passive"))
      (node (ref "R16") (pin "2") (pinfunction "2_2") (pintype "passive"))
      (node (ref "R17") (pin "2") (pinfunction "2_2") (pintype "passive"))
    )
    (net (code "51") (name "Net-(Q4-D)") (class "Default")
      (node (ref "C21") (pin "1") (pinfunction "1_1") (pintype "passive"))
      (node (ref "M4") (pin "2") (pinfunction "2_2") (pintype "passive"))
      (node (ref "Q4") (pin "3") (pinfunction "D_3") (pintype "passive"))
    )
    (net (code "52") (name "Net-(Q4-G)") (class "Default")
      (node (ref "Q4") (pin "1") (pinfunction "G_1") (pintype "passive"))
      (node (ref "R18") (pin "2") (pinfunction "2_2") (pintype "passive"))
      (node (ref "R19") (pin "2") (pinfunction "2_2") (pintype "passive"))
    )
    (net (code "53") (name "Net-(U1-LX)") (class "Default")
      (node (ref "L1") (pin "2") (pinfunction "2_2") (pintype "passive"))
      (node (ref "U1") (pin "5") (pinfunction "LX_5") (pintype "passive"))
    )
    (net (code "54") (name "Net-(U3-PD0)") (class "Default")
      (node (ref "U3") (pin "5") (pinfunction "PD0_5") (pintype "passive"))
      (node (ref "Y1") (pin "1") (pinfunction "1_1") (pintype "passive"))
    )
    (net (code "55") (name "Net-(U3-PD1)") (class "Default")
      (node (ref "U3") (pin "6") (pinfunction "PD1_6") (pintype "passive"))
      (node (ref "Y1") (pin "2") (pinfunction "2_2") (pintype "passive"))
    )
    (net (code "56") (name "Net-(U5-CPOUT)") (class "Default")
      (node (ref "C32") (pin "2") (pinfunction "2_2") (pintype "passive"))
      (node (ref "U5") (pin "20") (pinfunction "CPOUT_20") (pintype "passive"))
    )
    (net (code "57") (name "Net-(U5-REGOUT)") (class "Default")
      (node (ref "C35") (pin "1") (pinfunction "1_1") (pintype "passive"))
      (node (ref "U5") (pin "10") (pinfunction "REGOUT_10") (pintype "passive"))
    )
    (net (code "58") (name "VBAT") (class "Default")
      (node (ref "C18") (pin "2") (pinfunction "2_2") (pintype "passive"))
      (node (ref "C19") (pin "2") (pinfunction "2_2") (pintype "passive"))
      (node (ref "C20") (pin "2") (pinfunction "2_2") (pintype "passive"))
      (node (ref "C21") (pin "2") (pinfunction "2_2") (pintype "passive"))
      (node (ref "D8") (pin "1") (pinfunction "A_1") (pintype "passive"))
      (node (ref "KG1") (pin "2") (pinfunction "2_2") (pintype "passive"))
      (node (ref "KG1") (pin "5") (pinfunction "5_5") (pintype "passive"))
      (node (ref "M1") (pin "1") (pinfunction "1_1") (pintype "passive"))
      (node (ref "M2") (pin "1") (pinfunction "1_1") (pintype "passive"))
      (node (ref "M3") (pin "1") (pinfunction "1_1") (pintype "passive"))
      (node (ref "M4") (pin "1") (pinfunction "1_1") (pintype "passive"))
      (node (ref "R3") (pin "2") (pinfunction "2_2") (pintype "passive"))
    )
    (net (code "59") (name "unconnected-(D4-DO-Pad4)") (class "Default")
      (node (ref "D4") (pin "4") (pinfunction "DO_4") (pintype "passive+no_connect"))
    )
    (net (code "60") (name "unconnected-(KG1-Pad3)") (class "Default")
      (node (ref "KG1") (pin "3") (pinfunction "3_3") (pintype "passive"))
    )
    (net (code "61") (name "unconnected-(KG1-Pad6)") (class "Default")
      (node (ref "KG1") (pin "6") (pinfunction "6_6") (pintype "passive"))
    )
    (net (code "62") (name "unconnected-(U1-NC-Pad3)") (class "Default")
      (node (ref "U1") (pin "3") (pinfunction "NC_3") (pintype "passive"))
    )
    (net (code "63") (name "unconnected-(U3-PA0-Pad10)") (class "Default")
      (node (ref "U3") (pin "10") (pinfunction "PA0_10") (pintype "passive+no_connect"))
    )
    (net (code "64") (name "unconnected-(U3-PA15-Pad38)") (class "Default")
      (node (ref "U3") (pin "38") (pinfunction "PA15_38") (pintype "passive+no_connect"))
    )
    (net (code "65") (name "unconnected-(U3-PB3-Pad39)") (class "Default")
      (node (ref "U3") (pin "39") (pinfunction "PB3_39") (pintype "passive+no_connect"))
    )
    (net (code "66") (name "unconnected-(U3-PB4-Pad40)") (class "Default")
      (node (ref "U3") (pin "40") (pinfunction "PB4_40") (pintype "passive+no_connect"))
    )
    (net (code "67") (name "unconnected-(U3-PC15-Pad4)") (class "Default")
      (node (ref "U3") (pin "4") (pinfunction "PC15_4") (pintype "passive+no_connect"))
    )
    (net (code "68") (name "unconnected-(U5-A-CL-Pad7)") (class "Default")
      (node (ref "U5") (pin "7") (pinfunction "A-CL_7") (pintype "passive+no_connect"))
    )
    (net (code "69") (name "unconnected-(U5-A_DA-Pad6)") (class "Default")
      (node (ref "U5") (pin "6") (pinfunction "A_DA_6") (pintype "passive+no_connect"))
    )
    (net (code "70") (name "unconnected-(U5-CLKOUT-Pad22)") (class "Default")
      (node (ref "U5") (pin "22") (pinfunction "CLKOUT_22") (pintype "passive+no_connect"))
    )
    (net (code "71") (name "unconnected-(U5-NC-Pad2)") (class "Default")
      (node (ref "U5") (pin "2") (pinfunction "NC_2") (pintype "passive+no_connect"))
    )
    (net (code "72") (name "unconnected-(U5-NC-Pad3)") (class "Default")
      (node (ref "U5") (pin "3") (pinfunction "NC_3") (pintype "passive+no_connect"))
    )
    (net (code "73") (name "unconnected-(U5-NC-Pad4)") (class "Default")
      (node (ref "U5") (pin "4") (pinfunction "NC_4") (pintype "passive+no_connect"))
    )
    (net (code "74") (name "unconnected-(U5-NC-Pad5)") (class "Default")
      (node (ref "U5") (pin "5") (pinfunction "NC_5") (pintype "passive+no_connect"))
    )
    (net (code "75") (name "unconnected-(U5-NC-Pad14)") (class "Default")
      (node (ref "U5") (pin "14") (pinfunction "NC_14") (pintype "passive+no_connect"))
    )
    (net (code "76") (name "unconnected-(U5-NC-Pad15)") (class "Default")
      (node (ref "U5") (pin "15") (pinfunction "NC_15") (pintype "passive+no_connect"))
    )
    (net (code "77") (name "unconnected-(U5-NC-Pad16)") (class "Default")
      (node (ref "U5") (pin "16") (pinfunction "NC_16") (pintype "passive+no_connect"))
    )
    (net (code "78") (name "unconnected-(U5-NC-Pad17)") (class "Default")
      (node (ref "U5") (pin "17") (pinfunction "NC_17") (pintype "passive+no_connect"))
    )
    (net (code "79") (name "unconnected-(U5-RESV-Pad19)") (class "Default")
      (node (ref "U5") (pin "19") (pinfunction "RESV_19") (pintype "passive+no_connect"))
    )
    (net (code "80") (name "unconnected-(U5-RESV-Pad21)") (class "Default")
      (node (ref "U5") (pin "21") (pinfunction "RESV_21") (pintype "passive+no_connect"))
    )
  )
)
